# JTAG.net
KiCad netlist of a schematic drawn in Altium Designer
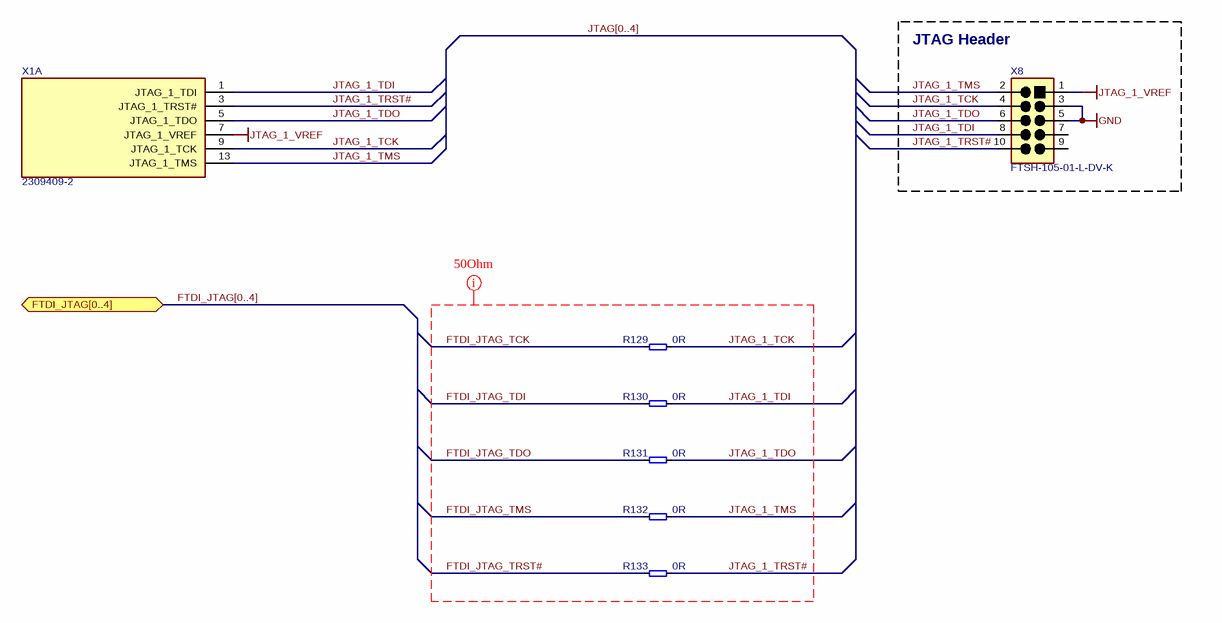
[diagram p0: JTAG.SchDoc]

(export (version "E")
  (design (tool "Eeschema 10.0.6"))
  (components
    (comp (ref "R129")
      (value "0R")
      (footprint "T_RESC0603X30N")
      (description "Resistor 0 ohm 63mW 1% 0603")
      (fields (field (name "TOLERANCE") "1%"))
      (libsource (lib "Dahlia Carrier Board") (part "R-0R-63mW-1%-0603"))
    )
    (comp (ref "R130")
      (value "0R")
      (footprint "T_RESC0603X30N")
      (description "Resistor 0 ohm 63mW 1% 0603")
      (fields (field (name "TOLERANCE") "1%"))
      (libsource (lib "Dahlia Carrier Board") (part "R-0R-63mW-1%-0603"))
    )
    (comp (ref "R131")
      (value "0R")
      (footprint "T_RESC0603X30N")
      (description "Resistor 0 ohm 63mW 1% 0603")
      (fields (field (name "TOLERANCE") "1%"))
      (libsource (lib "Dahlia Carrier Board") (part "R-0R-63mW-1%-0603"))
    )
    (comp (ref "R132")
      (value "0R")
      (footprint "T_RESC0603X30N")
      (description "Resistor 0 ohm 63mW 1% 0603")
      (fields (field (name "TOLERANCE") "1%"))
      (libsource (lib "Dahlia Carrier Board") (part "R-0R-63mW-1%-0603"))
    )
    (comp (ref "R133")
      (value "0R")
      (footprint "T_RESC0603X30N")
      (description "Resistor 0 ohm 63mW 1% 0603")
      (fields (field (name "TOLERANCE") "1%"))
      (libsource (lib "Dahlia Carrier Board") (part "R-0R-63mW-1%-0603"))
    )
    (comp (ref "X1")
      (value "2309409-2")
      (footprint "CON-TE-2309409-2-SOLDERABLE-STANDOFFS")
      (description "DDR4 SODIMM Socket, 260 pins, 5.2mm(H), 0.5mm Pitch")
      (libsource (lib "Dahlia Carrier Board") (part "CON-TE-2309409-2"))
    )
    (comp (ref "X8")
      (value "FTSH-105-01-L-DV-K")
      (footprint "T_Samtec_FTSH-105-01-L-DV")
      (description "Male Header, 10-Pin, 1.27mm Pitch")
      (fields (field (name "MANUFACTURER PART NO.") "FTSH-105-01-L-DV-K"))
      (libsource (lib "Dahlia Carrier Board") (part "CON-Samtec-FTSH-105-01-L-DV-1X10-1.27mm"))
    )
  )
  (nets
    (net (code "12") (name "/FTDI_JTAG_TCK") (class "Default")
      (node (ref "R129") (pin "1") (pinfunction "1_1") (pintype "passive"))
    )
    (net (code "13") (name "/FTDI_JTAG_TDI") (class "Default")
      (node (ref "R130") (pin "1") (pinfunction "1_1") (pintype "passive"))
    )
    (net (code "14") (name "/FTDI_JTAG_TDO") (class "Default")
      (node (ref "R131") (pin "1") (pinfunction "1_1") (pintype "passive"))
    )
    (net (code "15") (name "/FTDI_JTAG_TMS") (class "Default")
      (node (ref "R132") (pin "1") (pinfunction "1_1") (pintype "passive"))
    )
    (net (code "16") (name "/FTDI_JTAG_TRST#") (class "Default")
      (node (ref "R133") (pin "1") (pinfunction "1_1") (pintype "passive"))
    )
    (net (code "18") (name "/JTAG_1_TCK") (class "Default")
      (node (ref "R129") (pin "2") (pinfunction "2_2") (pintype "passive"))
      (node (ref "X1") (pin "9") (pinfunction "JTAG_1_TCK_9") (pintype "passive"))
      (node (ref "X8") (pin "4") (pinfunction "4_4") (pintype "passive"))
    )
    (net (code "19") (name "/JTAG_1_TDI") (class "Default")
      (node (ref "R130") (pin "2") (pinfunction "2_2") (pintype "passive"))
      (node (ref "X1") (pin "1") (pinfunction "JTAG_1_TDI_1") (pintype "passive"))
      (node (ref "X8") (pin "8") (pinfunction "8_8") (pintype "passive"))
    )
    (net (code "20") (name "/JTAG_1_TDO") (class "Default")
      (node (ref "R131") (pin "2") (pinfunction "2_2") (pintype "passive"))
      (node (ref "X1") (pin "5") (pinfunction "JTAG_1_TDO_5") (pintype "passive"))
      (node (ref "X8") (pin "6") (pinfunction "6_6") (pintype "passive"))
    )
    (net (code "21") (name "/JTAG_1_TMS") (class "Default")
      (node (ref "R132") (pin "2") (pinfunction "2_2") (pintype "passive"))
      (node (ref "X1") (pin "13") (pinfunction "JTAG_1_TMS_13") (pintype "passive"))
      (node (ref "X8") (pin "2") (pinfunction "2_2") (pintype "passive"))
    )
    (net (code "22") (name "/JTAG_1_TRST#") (class "Default")
      (node (ref "R133") (pin "2") (pinfunction "2_2") (pintype "passive"))
      (node (ref "X1") (pin "3") (pinfunction "JTAG_1_TRST#_3") (pintype "passive"))
      (node (ref "X8") (pin "10") (pinfunction "10_10") (pintype "passive"))
    )
    (net (code "23") (name "GND") (class "Default")
      (node (ref "X8") (pin "3") (pinfunction "3_3") (pintype "passive"))
      (node (ref "X8") (pin "5") (pinfunction "5_5") (pintype "passive"))
    )
    (net (code "24") (name "JTAG_1_VREF") (class "Default")
      (node (ref "X1") (pin "7") (pinfunction "JTAG_1_VREF_7") (pintype "passive"))
      (node (ref "X8") (pin "1") (pinfunction "1_1") (pintype "passive"))
    )
    (net (code "25") (name "unconnected-(X8-Pad7)") (class "Default")
      (node (ref "X8") (pin "7") (pinfunction "7_7") (pintype "passive"))
    )
    (net (code "26") (name "unconnected-(X8-Pad9)") (class "Default")
      (node (ref "X8") (pin "9") (pinfunction "9_9") (pintype "passive"))
    )
  )
)
